# 780-00038_rev1_Pg1_SCH_Flex_Pwr_Sply.net
KiCad netlist of a schematic drawn in Altium Designer
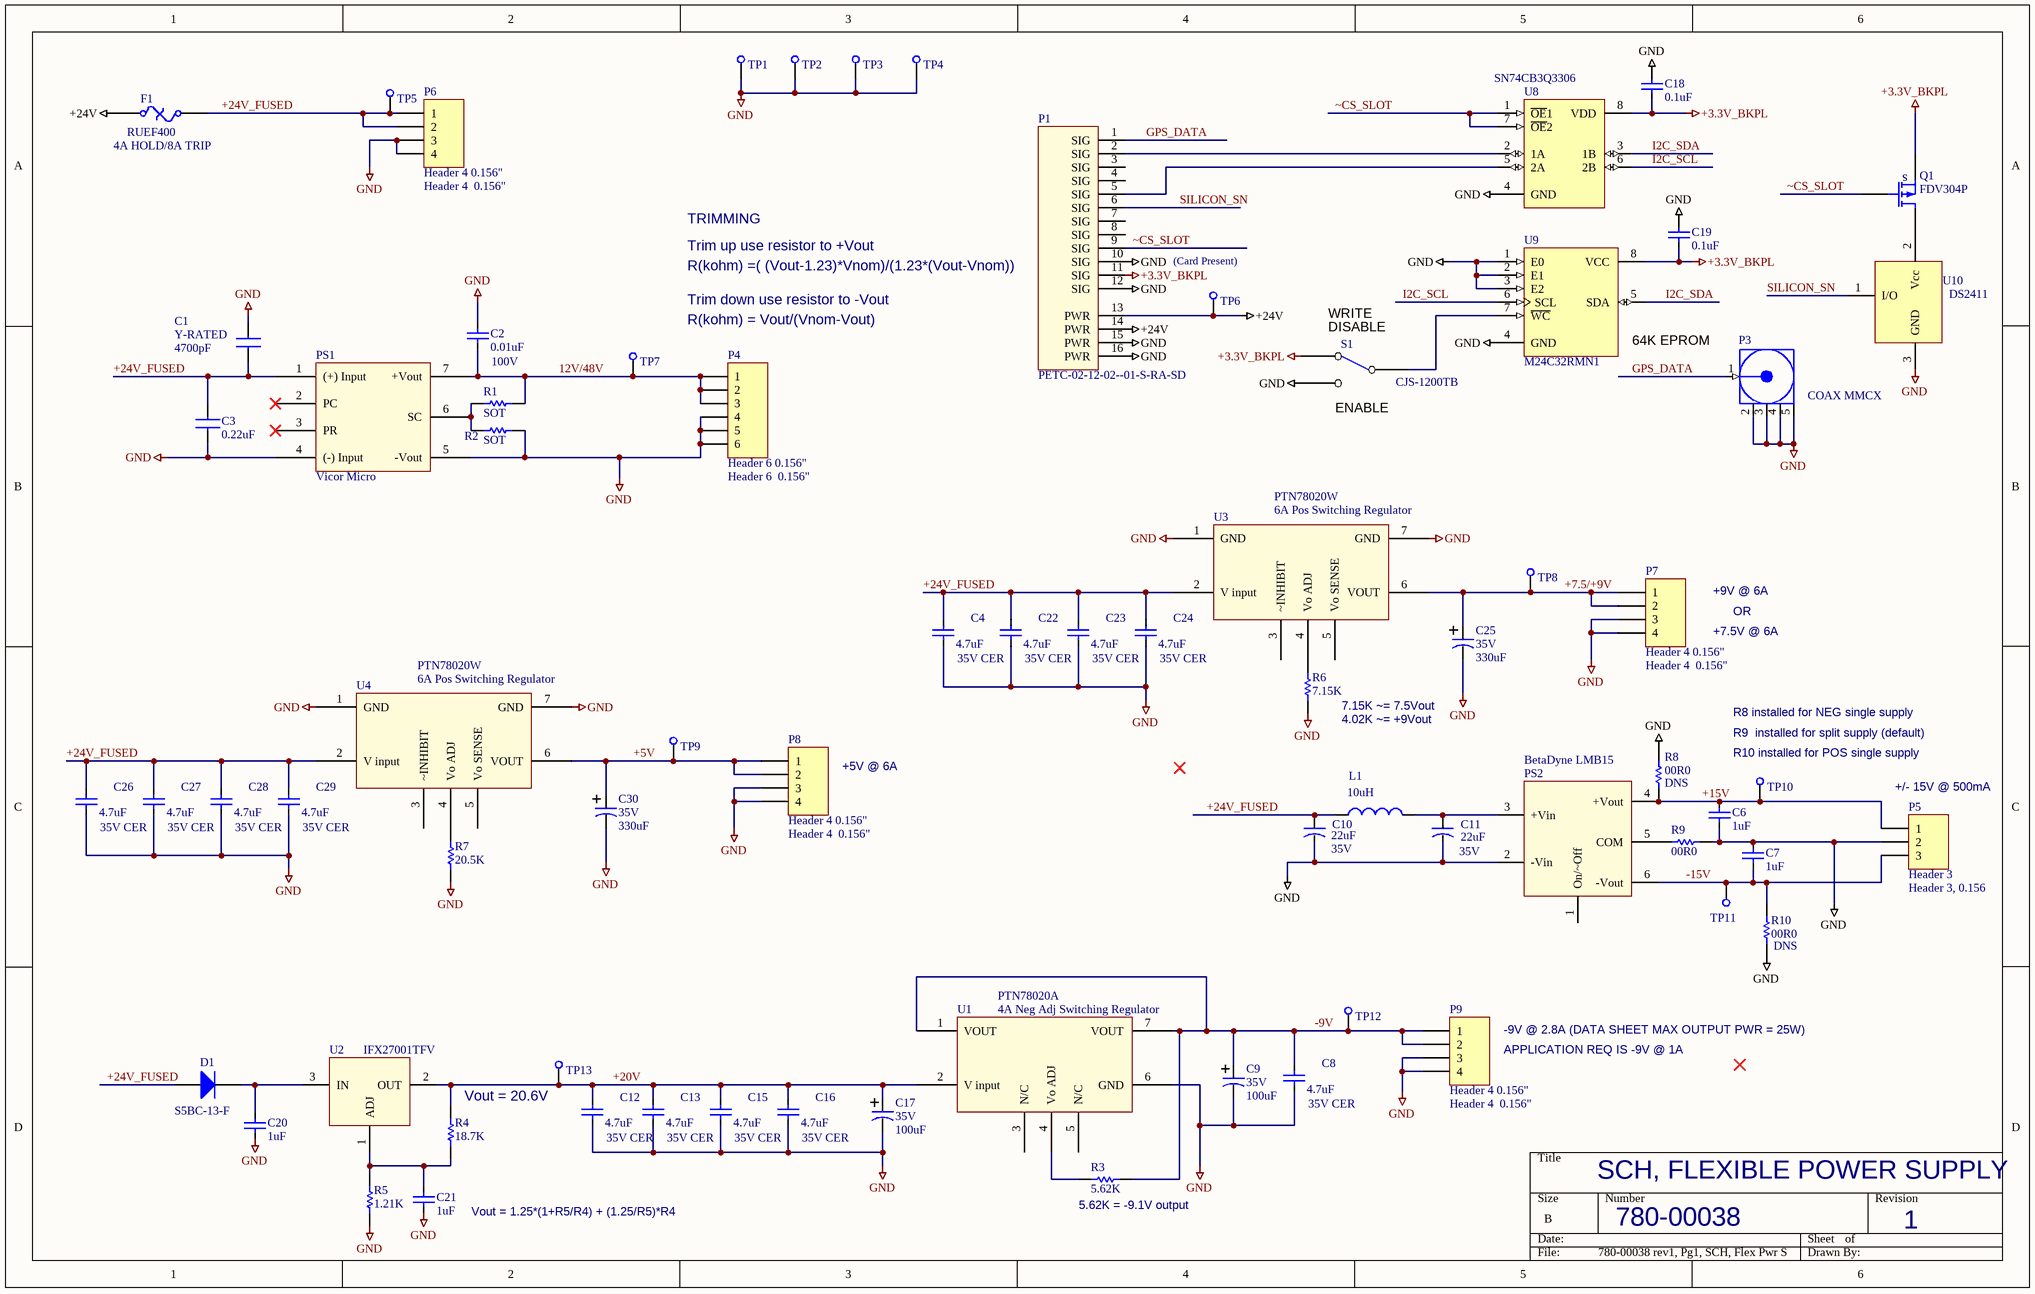
[diagram p0: 780-00038 rev1, Pg1, SCH, Flex Pwr Sply.SchDoc]

(export (version "E")
  (design (tool "Eeschema 10.0.6"))
  (components
    (comp (ref "C1")
      (value "Y-RATED")
      (footprint "1812")
      (fields (field (name "MANUFACTURER") "Murata") (field (name "ALTIUM_VALUE") "4700pF"))
      (libsource (lib "JON_1_Library") (part "CAP NP_DOUG"))
    )
    (comp (ref "C2")
      (value "100V")
      (footprint "SMD_0805")
      (description "Capacitor")
      (fields (field (name "MANUFACTURER") "Johanson") (field (name "ALTIUM_VALUE") "0.01uF"))
      (libsource (lib "Richs Schematic Components") (part "Cap SMD"))
    )
    (comp (ref "C3")
      (value "0.22uF")
      (footprint "1812")
      (fields (field (name "MANUFACTURER") "TDK"))
      (libsource (lib "JON_1_Library") (part "CAP NP_DOUG"))
    )
    (comp (ref "C4")
      (value "35V CER")
      (footprint "SMD_0805")
      (description "Capacitor")
      (fields (field (name "ALTIUM_VALUE") "4.7uF"))
      (libsource (lib "Richs Schematic Components") (part "Cap SMD"))
    )
    (comp (ref "C6")
      (value "1uF")
      (footprint "SMD_0805")
      (description "Capacitor")
      (fields (field (name "Comment") "Cap SMD"))
      (libsource (lib "Richs Schematic Components") (part "Cap SMD"))
    )
    (comp (ref "C7")
      (value "1uF")
      (footprint "SMD_0805")
      (description "Capacitor")
      (fields (field (name "Comment") "Cap SMD"))
      (libsource (lib "Richs Schematic Components") (part "Cap SMD"))
    )
    (comp (ref "C8")
      (value "35V CER")
      (footprint "SMD_0805")
      (description "Capacitor")
      (fields (field (name "ALTIUM_VALUE") "4.7uF"))
      (libsource (lib "Richs Schematic Components") (part "Cap SMD"))
    )
    (comp (ref "C9")
      (value "35V")
      (footprint "CAP, Thru Hole 8mm dia")
      (description "Radial Thru hole")
      (fields (field (name "ALTIUM_VALUE") "100uF"))
      (libsource (lib "Richs Schematic Components") (part "Cap Elec, 100 uF, 35V"))
    )
    (comp (ref "C10")
      (value "35V")
      (footprint "SMD_CAP_7343")
      (description "outline 6.0mm x 3.2mm")
      (fields (field (name "MANUFACTURER") "Kemet") (field (name "ALTIUM_VALUE") "22uF"))
      (libsource (lib "Richs Schematic Components") (part "Cap Tant 35V"))
    )
    (comp (ref "C11")
      (value "35V")
      (footprint "SMD_CAP_7343")
      (description "outline 6.0mm x 3.2mm")
      (fields (field (name "MANUFACTURER") "Kemet") (field (name "ALTIUM_VALUE") "22uF"))
      (libsource (lib "Richs Schematic Components") (part "Cap Tant 35V"))
    )
    (comp (ref "C12")
      (value "35V CER")
      (footprint "SMD_0805")
      (description "Capacitor")
      (fields (field (name "ALTIUM_VALUE") "4.7uF"))
      (libsource (lib "Richs Schematic Components") (part "Cap SMD"))
    )
    (comp (ref "C13")
      (value "35V CER")
      (footprint "SMD_0805")
      (description "Capacitor")
      (fields (field (name "ALTIUM_VALUE") "4.7uF"))
      (libsource (lib "Richs Schematic Components") (part "Cap SMD"))
    )
    (comp (ref "C15")
      (value "35V CER")
      (footprint "SMD_0805")
      (description "Capacitor")
      (fields (field (name "ALTIUM_VALUE") "4.7uF"))
      (libsource (lib "Richs Schematic Components") (part "Cap SMD"))
    )
    (comp (ref "C16")
      (value "35V CER")
      (footprint "SMD_0805")
      (description "Capacitor")
      (fields (field (name "ALTIUM_VALUE") "4.7uF"))
      (libsource (lib "Richs Schematic Components") (part "Cap SMD"))
    )
    (comp (ref "C17")
      (value "35V")
      (footprint "CAP, Thru Hole 8mm dia")
      (description "Radial Thru hole")
      (fields (field (name "ALTIUM_VALUE") "100uF"))
      (libsource (lib "Richs Schematic Components") (part "Cap Elec, 100 uF, 35V"))
    )
    (comp (ref "C18")
      (value "0.1uF")
      (footprint "SMD_0805")
      (description "Capacitor")
      (fields (field (name "MANUFACTURER") "AVX") (field (name "Comment") "Cap SMD"))
      (libsource (lib "Richs Schematic Components") (part "Cap SMD"))
    )
    (comp (ref "C19")
      (value "0.1uF")
      (footprint "SMD_0805")
      (description "Capacitor")
      (fields (field (name "MANUFACTURER") "AVX") (field (name "Comment") "Cap SMD"))
      (libsource (lib "Richs Schematic Components") (part "Cap SMD"))
    )
    (comp (ref "C20")
      (value "1uF")
      (footprint "SMD_0805")
      (description "Capacitor")
      (fields (field (name "Comment") "Cap SMD"))
      (libsource (lib "Richs Schematic Components") (part "Cap SMD"))
    )
    (comp (ref "C21")
      (value "1uF")
      (footprint "SMD_0805")
      (description "Capacitor")
      (fields (field (name "Comment") "Cap SMD"))
      (libsource (lib "Richs Schematic Components") (part "Cap SMD"))
    )
    (comp (ref "C22")
      (value "35V CER")
      (footprint "SMD_0805")
      (description "Capacitor")
      (fields (field (name "ALTIUM_VALUE") "4.7uF"))
      (libsource (lib "Richs Schematic Components") (part "Cap SMD"))
    )
    (comp (ref "C23")
      (value "35V CER")
      (footprint "SMD_0805")
      (description "Capacitor")
      (fields (field (name "ALTIUM_VALUE") "4.7uF"))
      (libsource (lib "Richs Schematic Components") (part "Cap SMD"))
    )
    (comp (ref "C24")
      (value "35V CER")
      (footprint "SMD_0805")
      (description "Capacitor")
      (fields (field (name "ALTIUM_VALUE") "4.7uF"))
      (libsource (lib "Richs Schematic Components") (part "Cap SMD"))
    )
    (comp (ref "C25")
      (value "35V")
      (footprint "CAP, Thru Hole 10mm dia")
      (description "Radial Thru hole")
      (fields (field (name "ALTIUM_VALUE") "330uF"))
      (libsource (lib "Richs Schematic Components") (part "Cap Elec, 330 uF, 35V"))
    )
    (comp (ref "C26")
      (value "35V CER")
      (footprint "SMD_0805")
      (description "Capacitor")
      (fields (field (name "ALTIUM_VALUE") "4.7uF"))
      (libsource (lib "Richs Schematic Components") (part "Cap SMD"))
    )
    (comp (ref "C27")
      (value "35V CER")
      (footprint "SMD_0805")
      (description "Capacitor")
      (fields (field (name "ALTIUM_VALUE") "4.7uF"))
      (libsource (lib "Richs Schematic Components") (part "Cap SMD"))
    )
    (comp (ref "C28")
      (value "35V CER")
      (footprint "SMD_0805")
      (description "Capacitor")
      (fields (field (name "ALTIUM_VALUE") "4.7uF"))
      (libsource (lib "Richs Schematic Components") (part "Cap SMD"))
    )
    (comp (ref "C29")
      (value "35V CER")
      (footprint "SMD_0805")
      (description "Capacitor")
      (fields (field (name "ALTIUM_VALUE") "4.7uF"))
      (libsource (lib "Richs Schematic Components") (part "Cap SMD"))
    )
    (comp (ref "C30")
      (value "35V")
      (footprint "CAP, Thru Hole 10mm dia")
      (description "Radial Thru hole")
      (fields (field (name "ALTIUM_VALUE") "330uF"))
      (libsource (lib "Richs Schematic Components") (part "Cap Elec, 330 uF, 35V"))
    )
    (comp (ref "D1")
      (value "S5BC-13-F")
      (footprint "SMC")
      (description "RECTIFIER GPP SMD 100V 5A SMC")
      (fields (field (name "MANUFACTURER") "Diodes Inc"))
      (libsource (lib "Miscellaneous Devices") (part "Diode"))
    )
    (comp (ref "F1")
      (value "RUEF400")
      (footprint "PolySwitch Radial 0.2")
      (description "PolySwitch RUE Series")
      (fields
        (field (name "MANUFACTURER") "Tyco Electronics")
        (field (name "ALTIUM_VALUE") "4A HOLD/8A TRIP")
      )
      (libsource (lib "Richs Schematic Components") (part "Fuse Thermal"))
    )
    (comp (ref "L1")
      (value "10uH")
      (footprint "Inductor TDC SLF")
      (description "Inductor")
      (fields (field (name "MANUFACTURER") "TDK") (field (name "Comment") "445-3869-1-ND"))
      (libsource (lib "Richs Schematic Components") (part "Inductor SMD 10uH 1.8A"))
    )
    (comp (ref "P1")
      (value "PETC-02-12-02--01-S-RA-SD")
      (footprint "PETC-02-12-02-01-RA")
      (description "SAMTEC, SIGNAL(12)+PWR(4)")
      (fields (field (name "MANUFACTURER") "SAMTEC"))
      (libsource (lib "Richs Schematic Components") (part "PETC-02-12-02--01-S-RA-SD"))
    )
    (comp (ref "P3")
      (value "COAX MMCX")
      (footprint "Miscellaneous Connectors:MMCX2.54-V5")
      (description "RF Coaxial PCB Connector, MMCX; Thru-Hole, Vertical Mount Plug,  50 Ohm Impedance")
      (fields (field (name "MANUFACTURER") "Emerson"))
      (libsource (lib "Richs Schematic Components") (part "COAX-M"))
    )
    (comp (ref "P4")
      (value "Header 6 0.156\"")
      (footprint "HDR 1X6 0.156\"")
      (description "Header, 6-Pin")
      (fields (field (name "MANUFACTURER") "Tyco") (field (name "ALTIUM_VALUE") "Header 6  0.156\""))
      (libsource (lib "Richs Schematic Components") (part "Header 6 0.156{dblquote}"))
    )
    (comp (ref "P5")
      (value "Header 3")
      (footprint "HDR 1X3 0.156\"")
      (description "Header, 3-Pin, 0.156")
      (fields (field (name "ALTIUM_VALUE") "Header 3, 0.156"))
      (libsource (lib "Richs Schematic Components") (part "Header 3, 0.156"))
    )
    (comp (ref "P6")
      (value "Header 4 0.156\"")
      (footprint "HDR 1X4 0.156\"")
      (description "Header, 4-Pin")
      (fields (field (name "MANUFACTURER") "Tyco") (field (name "ALTIUM_VALUE") "Header 4  0.156\""))
      (libsource (lib "Richs Schematic Components") (part "Header 4 0.156{dblquote}"))
    )
    (comp (ref "P7")
      (value "Header 4 0.156\"")
      (footprint "HDR 1X4 0.156\"")
      (description "Header, 4-Pin")
      (fields (field (name "MANUFACTURER") "Tyco") (field (name "ALTIUM_VALUE") "Header 4  0.156\""))
      (libsource (lib "Richs Schematic Components") (part "Header 4 0.156{dblquote}"))
    )
    (comp (ref "P8")
      (value "Header 4 0.156\"")
      (footprint "HDR 1X4 0.156\"")
      (description "Header, 4-Pin")
      (fields (field (name "MANUFACTURER") "Tyco") (field (name "ALTIUM_VALUE") "Header 4  0.156\""))
      (libsource (lib "Richs Schematic Components") (part "Header 4 0.156{dblquote}"))
    )
    (comp (ref "P9")
      (value "Header 4 0.156\"")
      (footprint "HDR 1X4 0.156\"")
      (description "Header, 4-Pin")
      (fields (field (name "MANUFACTURER") "Tyco") (field (name "ALTIUM_VALUE") "Header 4  0.156\""))
      (libsource (lib "Richs Schematic Components") (part "Header 4 0.156{dblquote}"))
    )
    (comp (ref "PS1")
      (value "Vicor Micro")
      (footprint "Vicor Micro SurfMate")
      (libsource (lib "Richs Schematic Components") (part "Vicor Micro"))
    )
    (comp (ref "PS2")
      (value "BetaDyne LMB15")
      (footprint "BetaDyne LNB15, DC/DC")
      (description "DC/DC LMB15 15W, Dual Output")
      (libsource (lib "Richs Schematic Components") (part "BetaDyne LMB15"))
    )
    (comp (ref "Q1")
      (value "FDV304P")
      (footprint "SMD_SOT23_3")
      (description "P-MOSFET LOGIC LEVEL")
      (fields (field (name "MANUFACTURER") "Fairchild"))
      (libsource (lib "Richs Schematic Components") (part "FDV304P"))
    )
    (comp (ref "R1")
      (value "SOT")
      (footprint "SMD_0805")
      (description "Resistor 0805")
      (fields (field (name "MANUFACTURER") "Vishay/Dale") (field (name "Comment") "Res 0805"))
      (libsource (lib "Richs Schematic Components") (part "Res SMD"))
    )
    (comp (ref "R2")
      (value "SOT")
      (footprint "SMD_0805")
      (description "Resistor 0805")
      (fields (field (name "MANUFACTURER") "Vishay/Dale") (field (name "Comment") "Res 0805"))
      (libsource (lib "Richs Schematic Components") (part "Res SMD"))
    )
    (comp (ref "R3")
      (value "5.62K")
      (footprint "SMD_0805")
      (description "Resistor 0805")
      (fields (field (name "MANUFACTURER") "Vishay/Dale") (field (name "Comment") "Res 0805"))
      (libsource (lib "Richs Schematic Components") (part "Res SMD"))
    )
    (comp (ref "R4")
      (value "18.7K")
      (footprint "SMD_0805")
      (description "Resistor 0805")
      (fields (field (name "MANUFACTURER") "Vishay/Dale") (field (name "Comment") "Res 0805"))
      (libsource (lib "Richs Schematic Components") (part "Res SMD"))
    )
    (comp (ref "R5")
      (value "1.21K")
      (footprint "SMD_0805")
      (description "Resistor 0805")
      (fields (field (name "MANUFACTURER") "Vishay/Dale") (field (name "Comment") "Res 0805"))
      (libsource (lib "Richs Schematic Components") (part "Res SMD"))
    )
    (comp (ref "R6")
      (value "7.15K")
      (footprint "SMD_0805")
      (description "Resistor 0805")
      (fields (field (name "MANUFACTURER") "Vishay/Dale") (field (name "Comment") "Res 0805"))
      (libsource (lib "Richs Schematic Components") (part "Res SMD"))
    )
    (comp (ref "R7")
      (value "20.5K")
      (footprint "SMD_0805")
      (description "Resistor 0805")
      (fields (field (name "MANUFACTURER") "Vishay/Dale") (field (name "Comment") "Res 0805"))
      (libsource (lib "Richs Schematic Components") (part "Res SMD"))
    )
    (comp (ref "R8")
      (value "DNS")
      (footprint "SMD_0805")
      (description "Resistor 0805")
      (fields (field (name "MANUFACTURER") "Vishay/Dale") (field (name "ALTIUM_VALUE") "00R0"))
      (libsource (lib "Richs Schematic Components") (part "Res SMD"))
    )
    (comp (ref "R9")
      (value "00R0")
      (footprint "SMD_0805")
      (description "Resistor 0805")
      (fields (field (name "MANUFACTURER") "Vishay/Dale") (field (name "Comment") "Res 0805"))
      (libsource (lib "Richs Schematic Components") (part "Res SMD"))
    )
    (comp (ref "R10")
      (value "DNS")
      (footprint "SMD_0805")
      (description "Resistor 0805")
      (fields (field (name "MANUFACTURER") "Vishay/Dale") (field (name "ALTIUM_VALUE") "00R0"))
      (libsource (lib "Richs Schematic Components") (part "Res SMD"))
    )
    (comp (ref "S1")
      (value "CJS-1200TB")
      (footprint "CAS-120B")
      (fields (field (name "MANUFACTURER") "Copal Electronics"))
      (libsource (lib "JON_1_Library") (part "SW_SPDT_DOUG"))
    )
    (comp (ref "TP1")
      (value "Test point")
      (footprint "Protel 99SE BANKS PCB:PAD_80D_052H")
      (description "Test Point")
      (fields (field (name "MANUFACTURER") "Keystone"))
      (libsource (lib "Richs Schematic Components") (part "Test point"))
    )
    (comp (ref "TP2")
      (value "Test point")
      (footprint "Protel 99SE BANKS PCB:PAD_80D_052H")
      (description "Test Point")
      (fields (field (name "MANUFACTURER") "Keystone"))
      (libsource (lib "Richs Schematic Components") (part "Test point"))
    )
    (comp (ref "TP3")
      (value "Test point")
      (footprint "Protel 99SE BANKS PCB:PAD_80D_052H")
      (description "Test Point")
      (fields (field (name "MANUFACTURER") "Keystone"))
      (libsource (lib "Richs Schematic Components") (part "Test point"))
    )
    (comp (ref "TP4")
      (value "Test point")
      (footprint "Protel 99SE BANKS PCB:PAD_80D_052H")
      (description "Test Point")
      (fields (field (name "MANUFACTURER") "Keystone"))
      (libsource (lib "Richs Schematic Components") (part "Test point"))
    )
    (comp (ref "TP5")
      (value "Test point")
      (footprint "Protel 99SE BANKS PCB:PAD_80D_052H")
      (description "Test Point")
      (fields (field (name "MANUFACTURER") "Keystone"))
      (libsource (lib "Richs Schematic Components") (part "Test point"))
    )
    (comp (ref "TP6")
      (value "Test point")
      (footprint "Protel 99SE BANKS PCB:PAD_80D_052H")
      (description "Test Point")
      (fields (field (name "MANUFACTURER") "Keystone"))
      (libsource (lib "Richs Schematic Components") (part "Test point"))
    )
    (comp (ref "TP7")
      (value "Test point")
      (footprint "Protel 99SE BANKS PCB:PAD_80D_052H")
      (description "Test Point")
      (fields (field (name "MANUFACTURER") "Keystone"))
      (libsource (lib "Richs Schematic Components") (part "Test point"))
    )
    (comp (ref "TP8")
      (value "Test point")
      (footprint "Protel 99SE BANKS PCB:PAD_80D_052H")
      (description "Test Point")
      (fields (field (name "MANUFACTURER") "Keystone"))
      (libsource (lib "Richs Schematic Components") (part "Test point"))
    )
    (comp (ref "TP9")
      (value "Test point")
      (footprint "Protel 99SE BANKS PCB:PAD_80D_052H")
      (description "Test Point")
      (fields (field (name "MANUFACTURER") "Keystone"))
      (libsource (lib "Richs Schematic Components") (part "Test point"))
    )
    (comp (ref "TP10")
      (value "Test point")
      (footprint "Protel 99SE BANKS PCB:PAD_80D_052H")
      (description "Test Point")
      (fields (field (name "MANUFACTURER") "Keystone"))
      (libsource (lib "Richs Schematic Components") (part "Test point"))
    )
    (comp (ref "TP11")
      (value "Test point")
      (footprint "Protel 99SE BANKS PCB:PAD_80D_052H")
      (description "Test Point")
      (fields (field (name "MANUFACTURER") "Keystone"))
      (libsource (lib "Richs Schematic Components") (part "Test point"))
    )
    (comp (ref "TP12")
      (value "Test point")
      (footprint "Protel 99SE BANKS PCB:PAD_80D_052H")
      (description "Test Point")
      (fields (field (name "MANUFACTURER") "Keystone"))
      (libsource (lib "Richs Schematic Components") (part "Test point"))
    )
    (comp (ref "TP13")
      (value "Test point")
      (footprint "Protel 99SE BANKS PCB:PAD_80D_052H")
      (description "Test Point")
      (fields (field (name "MANUFACTURER") "Keystone"))
      (libsource (lib "Richs Schematic Components") (part "Test point"))
    )
    (comp (ref "U1")
      (value "4A Neg Adj Switching Regulator")
      (footprint "TEXAS Inst Switching Regulator")
      (description "Neg Adj Switching Regulator")
      (fields (field (name "ALTIUM_VALUE") "PTN78020A"))
      (libsource (lib "Richs Schematic Components") (part "PTN78020A"))
    )
    (comp (ref "U2")
      (value "IFX27001TFV")
      (footprint "TO-252(D-PAK)  PowerPAD")
      (description "IFX27001")
      (fields (field (name "MANUFACTURER") "Infineon") (field (name "Comment") "Voltage Reg, Adj"))
      (libsource (lib "Richs Schematic Components") (part "Voltage Reg, Adjustable"))
    )
    (comp (ref "U3")
      (value "6A Pos Switching Regulator")
      (footprint "TEXAS Inst Switching Regulator")
      (description "Pos Adj Switching Regulator")
      (fields (field (name "ALTIUM_VALUE") "PTN78020W"))
      (libsource (lib "Richs Schematic Components") (part "PTN78020W"))
    )
    (comp (ref "U4")
      (value "6A Pos Switching Regulator")
      (footprint "TEXAS Inst Switching Regulator")
      (description "Pos Adj Switching Regulator")
      (fields (field (name "ALTIUM_VALUE") "PTN78020W"))
      (libsource (lib "Richs Schematic Components") (part "PTN78020W"))
    )
    (comp (ref "U8")
      (value "SN74CB3Q3306")
      (footprint "PW008_N")
      (description "Dual FET Bus Switch")
      (fields (field (name "MANUFACTURER") "TI") (field (name "Comment") "SN74CBT3306PWLE"))
      (libsource (lib "TI Logic Switch") (part "SN74CBT3306PWLE"))
    )
    (comp (ref "U9")
      (value "M24C32RMN1")
      (footprint "SOP8_N")
      (description "32 Kbit Serial I²C Bus EEPROM")
      (libsource (lib "ST Memory EEPROM Serial") (part "M24C32RMN1"))
    )
    (comp (ref "U10")
      (value "DS2411")
      (footprint "SMD_SOT23_3")
      (description "Silicon Serial Number")
      (fields (field (name "MANUFACTURER") "Dallas"))
      (libsource (lib "Richs Schematic Components") (part "DS2411"))
    )
  )
  (nets
    (net (code "1") (name "+3.3V_BKPL") (class "Default")
      (node (ref "C18") (pin "1") (pinfunction "1_1") (pintype "passive"))
      (node (ref "C19") (pin "1") (pinfunction "1_1") (pintype "passive"))
      (node (ref "P1") (pin "11") (pinfunction "SIG_11") (pintype "passive"))
      (node (ref "Q1") (pin "2") (pinfunction "S_2") (pintype "passive"))
      (node (ref "S1") (pin "3") (pinfunction "NC_3") (pintype "passive"))
      (node (ref "U8") (pin "8") (pinfunction "VDD_8") (pintype "power_in"))
      (node (ref "U9") (pin "8") (pinfunction "VCC_8") (pintype "power_in"))
    )
    (net (code "2") (name "+24V") (class "Default")
      (node (ref "F1") (pin "1") (pinfunction "1_1") (pintype "passive"))
      (node (ref "P1") (pin "13") (pinfunction "PWR_13") (pintype "passive"))
      (node (ref "P1") (pin "14") (pinfunction "PWR_14") (pintype "passive"))
      (node (ref "TP6") (pin "1") (pinfunction "TP_1") (pintype "passive"))
    )
    (net (code "3") (name "/+5V") (class "Default")
      (node (ref "C30") (pin "1") (pinfunction "1_1") (pintype "passive"))
      (node (ref "P8") (pin "1") (pinfunction "1_1") (pintype "passive"))
      (node (ref "P8") (pin "2") (pinfunction "2_2") (pintype "passive"))
      (node (ref "TP9") (pin "1") (pinfunction "TP_1") (pintype "passive"))
      (node (ref "U4") (pin "6") (pinfunction "VOUT_6") (pintype "passive"))
    )
    (net (code "4") (name "/+7.5{slash}+9V") (class "Default")
      (node (ref "C25") (pin "1") (pinfunction "1_1") (pintype "passive"))
      (node (ref "P7") (pin "1") (pinfunction "1_1") (pintype "passive"))
      (node (ref "P7") (pin "2") (pinfunction "2_2") (pintype "passive"))
      (node (ref "TP8") (pin "1") (pinfunction "TP_1") (pintype "passive"))
      (node (ref "U3") (pin "6") (pinfunction "VOUT_6") (pintype "passive"))
    )
    (net (code "5") (name "/+15V") (class "Default")
      (node (ref "C6") (pin "2") (pinfunction "2_2") (pintype "passive"))
      (node (ref "P5") (pin "1") (pinfunction "1_1") (pintype "passive"))
      (node (ref "PS2") (pin "4") (pinfunction "+Vout_4") (pintype "passive"))
      (node (ref "R8") (pin "1") (pinfunction "1_1") (pintype "passive"))
      (node (ref "TP10") (pin "1") (pinfunction "TP_1") (pintype "passive"))
    )
    (net (code "6") (name "/+20V") (class "Default")
      (node (ref "C12") (pin "2") (pinfunction "2_2") (pintype "passive"))
      (node (ref "C13") (pin "2") (pinfunction "2_2") (pintype "passive"))
      (node (ref "C15") (pin "2") (pinfunction "2_2") (pintype "passive"))
      (node (ref "C16") (pin "2") (pinfunction "2_2") (pintype "passive"))
      (node (ref "C17") (pin "1") (pinfunction "1_1") (pintype "passive"))
      (node (ref "R4") (pin "2") (pinfunction "2_2") (pintype "passive"))
      (node (ref "TP13") (pin "1") (pinfunction "TP_1") (pintype "passive"))
      (node (ref "U1") (pin "2") (pinfunction "V_input_2") (pintype "passive"))
      (node (ref "U2") (pin "2") (pinfunction "OUT_2") (pintype "passive"))
    )
    (net (code "7") (name "/+24V_FUSED") (class "Default")
      (node (ref "C1") (pin "2") (pinfunction "2_2") (pintype "passive"))
      (node (ref "C10") (pin "pos") (pinfunction "1_pos") (pintype "passive"))
      (node (ref "C22") (pin "2") (pinfunction "2_2") (pintype "passive"))
      (node (ref "C23") (pin "2") (pinfunction "2_2") (pintype "passive"))
      (node (ref "C24") (pin "2") (pinfunction "2_2") (pintype "passive"))
      (node (ref "C26") (pin "2") (pinfunction "2_2") (pintype "passive"))
      (node (ref "C27") (pin "2") (pinfunction "2_2") (pintype "passive"))
      (node (ref "C28") (pin "2") (pinfunction "2_2") (pintype "passive"))
      (node (ref "C29") (pin "2") (pinfunction "2_2") (pintype "passive"))
      (node (ref "C3") (pin "2") (pinfunction "2_2") (pintype "passive"))
      (node (ref "C4") (pin "2") (pinfunction "2_2") (pintype "passive"))
      (node (ref "D1") (pin "1") (pinfunction "A_1") (pintype "passive"))
      (node (ref "F1") (pin "2") (pinfunction "2_2") (pintype "passive"))
      (node (ref "L1") (pin "1") (pinfunction "1_1") (pintype "passive"))
      (node (ref "P6") (pin "1") (pinfunction "1_1") (pintype "passive"))
      (node (ref "P6") (pin "2") (pinfunction "2_2") (pintype "passive"))
      (node (ref "PS1") (pin "1") (pinfunction "(+)_Input_1") (pintype "passive"))
      (node (ref "TP5") (pin "1") (pinfunction "TP_1") (pintype "passive"))
      (node (ref "U3") (pin "2") (pinfunction "V_input_2") (pintype "passive"))
      (node (ref "U4") (pin "2") (pinfunction "V_input_2") (pintype "passive"))
    )
    (net (code "8") (name "/-9V") (class "Default")
      (node (ref "C8") (pin "2") (pinfunction "2_2") (pintype "passive"))
      (node (ref "C9") (pin "1") (pinfunction "1_1") (pintype "passive"))
      (node (ref "P9") (pin "1") (pinfunction "1_1") (pintype "passive"))
      (node (ref "P9") (pin "2") (pinfunction "2_2") (pintype "passive"))
      (node (ref "R3") (pin "2") (pinfunction "2_2") (pintype "passive"))
      (node (ref "TP12") (pin "1") (pinfunction "TP_1") (pintype "passive"))
      (node (ref "U1") (pin "1") (pinfunction "VOUT_1") (pintype "passive"))
      (node (ref "U1") (pin "7") (pinfunction "VOUT_7") (pintype "passive"))
    )
    (net (code "9") (name "/-15V") (class "Default")
      (node (ref "C7") (pin "1") (pinfunction "1_1") (pintype "passive"))
      (node (ref "P5") (pin "3") (pinfunction "3_3") (pintype "passive"))
      (node (ref "PS2") (pin "6") (pinfunction "-Vout_6") (pintype "passive"))
      (node (ref "R10") (pin "2") (pinfunction "2_2") (pintype "passive"))
      (node (ref "TP11") (pin "1") (pinfunction "TP_1") (pintype "passive"))
    )
    (net (code "10") (name "/12V{slash}48V") (class "Default")
      (node (ref "C2") (pin "1") (pinfunction "1_1") (pintype "passive"))
      (node (ref "P4") (pin "1") (pinfunction "1_1") (pintype "passive"))
      (node (ref "P4") (pin "2") (pinfunction "2_2") (pintype "passive"))
      (node (ref "P4") (pin "3") (pinfunction "3_3") (pintype "passive"))
      (node (ref "PS1") (pin "7") (pinfunction "+Vout_7") (pintype "passive"))
      (node (ref "R1") (pin "2") (pinfunction "2_2") (pintype "passive"))
      (node (ref "TP7") (pin "1") (pinfunction "TP_1") (pintype "passive"))
    )
    (net (code "11") (name "/GPS_DATA") (class "Default")
      (node (ref "P1") (pin "1") (pinfunction "SIG_1") (pintype "passive"))
      (node (ref "P3") (pin "1") (pinfunction "Signal_1") (pintype "input"))
    )
    (net (code "12") (name "/I2C_SCL") (class "Default")
      (node (ref "U8") (pin "6") (pinfunction "2B_6") (pintype "bidirectional"))
      (node (ref "U9") (pin "6") (pinfunction "SCL_6") (pintype "input"))
    )
    (net (code "13") (name "/I2C_SDA") (class "Default")
      (node (ref "U8") (pin "3") (pinfunction "1B_3") (pintype "bidirectional"))
      (node (ref "U9") (pin "5") (pinfunction "SDA_5") (pintype "bidirectional"))
    )
    (net (code "14") (name "/SILICON_SN") (class "Default")
      (node (ref "P1") (pin "6") (pinfunction "SIG_6") (pintype "passive"))
      (node (ref "U10") (pin "1") (pinfunction "I/O_1") (pintype "passive"))
    )
    (net (code "15") (name "/~CS_SLOT") (class "Default")
      (node (ref "P1") (pin "9") (pinfunction "SIG_9") (pintype "passive"))
      (node (ref "Q1") (pin "1") (pinfunction "G_1") (pintype "passive"))
      (node (ref "U8") (pin "1") (pinfunction "~{OE}1_1") (pintype "input"))
      (node (ref "U8") (pin "7") (pinfunction "~{OE}2_7") (pintype "input"))
    )
    (net (code "16") (name "GND") (class "Default")
      (node (ref "C1") (pin "1") (pinfunction "1_1") (pintype "passive"))
      (node (ref "C10") (pin "neg") (pinfunction "2_neg") (pintype "passive"))
      (node (ref "C11") (pin "neg") (pinfunction "2_neg") (pintype "passive"))
      (node (ref "C12") (pin "1") (pinfunction "1_1") (pintype "passive"))
      (node (ref "C13") (pin "1") (pinfunction "1_1") (pintype "passive"))
      (node (ref "C15") (pin "1") (pinfunction "1_1") (pintype "passive"))
      (node (ref "C16") (pin "1") (pinfunction "1_1") (pintype "passive"))
      (node (ref "C17") (pin "2") (pinfunction "2_2") (pintype "passive"))
      (node (ref "C18") (pin "2") (pinfunction "2_2") (pintype "passive"))
      (node (ref "C19") (pin "2") (pinfunction "2_2") (pintype "passive"))
      (node (ref "C2") (pin "2") (pinfunction "2_2") (pintype "passive"))
      (node (ref "C20") (pin "1") (pinfunction "1_1") (pintype "passive"))
      (node (ref "C21") (pin "1") (pinfunction "1_1") (pintype "passive"))
      (node (ref "C22") (pin "1") (pinfunction "1_1") (pintype "passive"))
      (node (ref "C23") (pin "1") (pinfunction "1_1") (pintype "passive"))
      (node (ref "C24") (pin "1") (pinfunction "1_1") (pintype "passive"))
      (node (ref "C25") (pin "2") (pinfunction "2_2") (pintype "passive"))
      (node (ref "C26") (pin "1") (pinfunction "1_1") (pintype "passive"))
      (node (ref "C27") (pin "1") (pinfunction "1_1") (pintype "passive"))
      (node (ref "C28") (pin "1") (pinfunction "1_1") (pintype "passive"))
      (node (ref "C29") (pin "1") (pinfunction "1_1") (pintype "passive"))
      (node (ref "C3") (pin "1") (pinfunction "1_1") (pintype "passive"))
      (node (ref "C30") (pin "2") (pinfunction "2_2") (pintype "passive"))
      (node (ref "C4") (pin "1") (pinfunction "1_1") (pintype "passive"))
      (node (ref "C6") (pin "1") (pinfunction "1_1") (pintype "passive"))
      (node (ref "C7") (pin "2") (pinfunction "2_2") (pintype "passive"))
      (node (ref "C8") (pin "1") (pinfunction "1_1") (pintype "passive"))
      (node (ref "C9") (pin "2") (pinfunction "2_2") (pintype "passive"))
      (node (ref "P1") (pin "10") (pinfunction "SIG_10") (pintype "passive"))
      (node (ref "P1") (pin "12") (pinfunction "SIG_12") (pintype "passive"))
      (node (ref "P1") (pin "15") (pinfunction "PWR_15") (pintype "passive"))
      (node (ref "P1") (pin "16") (pinfunction "PWR_16") (pintype "passive"))
      (node (ref "P3") (pin "2") (pinfunction "GND_2") (pintype "power_in"))
      (node (ref "P3") (pin "3") (pinfunction "GND_3") (pintype "power_in"))
      (node (ref "P3") (pin "4") (pinfunction "GND_4") (pintype "power_in"))
      (node (ref "P3") (pin "5") (pinfunction "GND_5") (pintype "power_in"))
      (node (ref "P4") (pin "4") (pinfunction "4_4") (pintype "passive"))
      (node (ref "P4") (pin "5") (pinfunction "5_5") (pintype "passive"))
      (node (ref "P4") (pin "6") (pinfunction "6_6") (pintype "passive"))
      (node (ref "P5") (pin "2") (pinfunction "2_2") (pintype "passive"))
      (node (ref "P6") (pin "3") (pinfunction "3_3") (pintype "passive"))
      (node (ref "P6") (pin "4") (pinfunction "4_4") (pintype "passive"))
      (node (ref "P7") (pin "3") (pinfunction "3_3") (pintype "passive"))
      (node (ref "P7") (pin "4") (pinfunction "4_4") (pintype "passive"))
      (node (ref "P8") (pin "3") (pinfunction "3_3") (pintype "passive"))
      (node (ref "P8") (pin "4") (pinfunction "4_4") (pintype "passive"))
      (node (ref "P9") (pin "3") (pinfunction "3_3") (pintype "passive"))
      (node (ref "P9") (pin "4") (pinfunction "4_4") (pintype "passive"))
      (node (ref "PS1") (pin "4") (pinfunction "(-)_Input_4") (pintype "passive"))
      (node (ref "PS1") (pin "5") (pinfunction "-Vout_5") (pintype "passive"))
      (node (ref "PS2") (pin "2") (pinfunction "-Vin_2") (pintype "passive"))
      (node (ref "R10") (pin "1") (pinfunction "1_1") (pintype "passive"))
      (node (ref "R2") (pin "2") (pinfunction "2_2") (pintype "passive"))
      (node (ref "R5") (pin "1") (pinfunction "1_1") (pintype "passive"))
      (node (ref "R6") (pin "1") (pinfunction "1_1") (pintype "passive"))
      (node (ref "R7") (pin "1") (pinfunction "1_1") (pintype "passive"))
      (node (ref "R8") (pin "2") (pinfunction "2_2") (pintype "passive"))
      (node (ref "R9") (pin "2") (pinfunction "2_2") (pintype "passive"))
      (node (ref "S1") (pin "1") (pinfunction "NO_1") (pintype "passive"))
      (node (ref "TP1") (pin "1") (pinfunction "TP_1") (pintype "passive"))
      (node (ref "TP2") (pin "1") (pinfunction "TP_1") (pintype "passive"))
      (node (ref "TP3") (pin "1") (pinfunction "TP_1") (pintype "passive"))
      (node (ref "TP4") (pin "1") (pinfunction "TP_1") (pintype "passive"))
      (node (ref "U1") (pin "6") (pinfunction "GND_6") (pintype "passive"))
      (node (ref "U10") (pin "3") (pinfunction "GND_3") (pintype "passive"))
      (node (ref "U3") (pin "1") (pinfunction "GND_1") (pintype "passive"))
      (node (ref "U3") (pin "7") (pinfunction "GND_7") (pintype "passive"))
      (node (ref "U4") (pin "1") (pinfunction "GND_1") (pintype "passive"))
      (node (ref "U4") (pin "7") (pinfunction "GND_7") (pintype "passive"))
      (node (ref "U8") (pin "4") (pinfunction "GND_4") (pintype "power_in"))
      (node (ref "U9") (pin "1") (pinfunction "E0_1") (pintype "input"))
      (node (ref "U9") (pin "2") (pinfunction "E1_2") (pintype "input"))
      (node (ref "U9") (pin "3") (pinfunction "E2_3") (pintype "input"))
      (node (ref "U9") (pin "4") (pinfunction "GND_4") (pintype "power_in"))
    )
    (net (code "17") (name "Net-(C11-1)") (class "Default")
      (node (ref "C11") (pin "pos") (pinfunction "1_pos") (pintype "passive"))
      (node (ref "L1") (pin "2") (pinfunction "2_2") (pintype "passive"))
      (node (ref "PS2") (pin "3") (pinfunction "+Vin_3") (pintype "passive"))
    )
    (net (code "18") (name "Net-(D1-K)") (class "Default")
      (node (ref "C20") (pin "2") (pinfunction "2_2") (pintype "passive"))
      (node (ref "D1") (pin "2") (pinfunction "K_2") (pintype "passive"))
      (node (ref "U2") (pin "3") (pinfunction "IN_3") (pintype "passive"))
    )
    (net (code "19") (name "Net-(PS1-SC)") (class "Default")
      (node (ref "PS1") (pin "6") (pinfunction "SC_6") (pintype "passive"))
      (node (ref "R1") (pin "1") (pinfunction "1_1") (pintype "passive"))
      (node (ref "R2") (pin "1") (pinfunction "1_1") (pintype "passive"))
    )
    (net (code "20") (name "Net-(PS2-COM)") (class "Default")
      (node (ref "PS2") (pin "5") (pinfunction "COM_5") (pintype "passive"))
      (node (ref "R9") (pin "1") (pinfunction "1_1") (pintype "passive"))
    )
    (net (code "21") (name "Net-(Q1-D)") (class "Default")
      (node (ref "Q1") (pin "3") (pinfunction "D_3") (pintype "passive"))
      (node (ref "U10") (pin "2") (pinfunction "Vcc_2") (pintype "passive"))
    )
    (net (code "22") (name "Net-(S1-COM)") (class "Default")
      (node (ref "S1") (pin "2") (pinfunction "COM_2") (pintype "passive"))
      (node (ref "U9") (pin "7") (pinfunction "~{WC}_7") (pintype "input"))
    )
    (net (code "23") (name "Net-(U1-Vo_ADJ)") (class "Default")
      (node (ref "R3") (pin "1") (pinfunction "1_1") (pintype "passive"))
      (node (ref "U1") (pin "4") (pinfunction "Vo_ADJ_4") (pintype "passive"))
    )
    (net (code "24") (name "Net-(U2-ADJ)") (class "Default")
      (node (ref "C21") (pin "2") (pinfunction "2_2") (pintype "passive"))
      (node (ref "R4") (pin "1") (pinfunction "1_1") (pintype "passive"))
      (node (ref "R5") (pin "2") (pinfunction "2_2") (pintype "passive"))
      (node (ref "U2") (pin "1") (pinfunction "ADJ_1") (pintype "passive"))
    )
    (net (code "25") (name "Net-(U3-Vo_ADJ)") (class "Default")
      (node (ref "R6") (pin "2") (pinfunction "2_2") (pintype "passive"))
      (node (ref "U3") (pin "4") (pinfunction "Vo_ADJ_4") (pintype "passive"))
    )
    (net (code "26") (name "Net-(U4-Vo_ADJ)") (class "Default")
      (node (ref "R7") (pin "2") (pinfunction "2_2") (pintype "passive"))
      (node (ref "U4") (pin "4") (pinfunction "Vo_ADJ_4") (pintype "passive"))
    )
    (net (code "27") (name "Net-(U8-1A)") (class "Default")
      (node (ref "P1") (pin "2") (pinfunction "SIG_2") (pintype "passive"))
      (node (ref "U8") (pin "2") (pinfunction "1A_2") (pintype "bidirectional"))
    )
    (net (code "28") (name "Net-(U8-2A)") (class "Default")
      (node (ref "P1") (pin "5") (pinfunction "SIG_5") (pintype "passive"))
      (node (ref "U8") (pin "5") (pinfunction "2A_5") (pintype "bidirectional"))
    )
    (net (code "29") (name "unconnected-(P1-SIG-Pad3)") (class "Default")
      (node (ref "P1") (pin "3") (pinfunction "SIG_3") (pintype "passive"))
    )
    (net (code "30") (name "unconnected-(P1-SIG-Pad4)") (class "Default")
      (node (ref "P1") (pin "4") (pinfunction "SIG_4") (pintype "passive"))
    )
    (net (code "31") (name "unconnected-(P1-SIG-Pad7)") (class "Default")
      (node (ref "P1") (pin "7") (pinfunction "SIG_7") (pintype "passive"))
    )
    (net (code "32") (name "unconnected-(P1-SIG-Pad8)") (class "Default")
      (node (ref "P1") (pin "8") (pinfunction "SIG_8") (pintype "passive"))
    )
    (net (code "33") (name "unconnected-(PS1-PC-Pad2)") (class "Default")
      (node (ref "PS1") (pin "2") (pinfunction "PC_2") (pintype "passive+no_connect"))
    )
    (net (code "34") (name "unconnected-(PS1-PR-Pad3)") (class "Default")
      (node (ref "PS1") (pin "3") (pinfunction "PR_3") (pintype "passive+no_connect"))
    )
    (net (code "35") (name "unconnected-(PS2-On{slash}~Off-Pad1)") (class "Default")
      (node (ref "PS2") (pin "1") (pinfunction "On/~Off_1") (pintype "passive"))
    )
    (net (code "36") (name "unconnected-(U1-N{slash}C-Pad3)") (class "Default")
      (node (ref "U1") (pin "3") (pinfunction "N/C_3") (pintype "passive"))
    )
    (net (code "37") (name "unconnected-(U1-N{slash}C-Pad5)") (class "Default")
      (node (ref "U1") (pin "5") (pinfunction "N/C_5") (pintype "passive"))
    )
    (net (code "38") (name "unconnected-(U3-Vo_SENSE-Pad5)") (class "Default")
      (node (ref "U3") (pin "5") (pinfunction "Vo_SENSE_5") (pintype "passive"))
    )
    (net (code "39") (name "unconnected-(U3-~INHIBIT-Pad3)") (class "Default")
      (node (ref "U3") (pin "3") (pinfunction "~INHIBIT_3") (pintype "passive"))
    )
    (net (code "40") (name "unconnected-(U4-Vo_SENSE-Pad5)") (class "Default")
      (node (ref "U4") (pin "5") (pinfunction "Vo_SENSE_5") (pintype "passive"))
    )
    (net (code "41") (name "unconnected-(U4-~INHIBIT-Pad3)") (class "Default")
      (node (ref "U4") (pin "3") (pinfunction "~INHIBIT_3") (pintype "passive"))
    )
  )
)
